# audio_V1.net
KiCad netlist of a schematic drawn in EAGLE
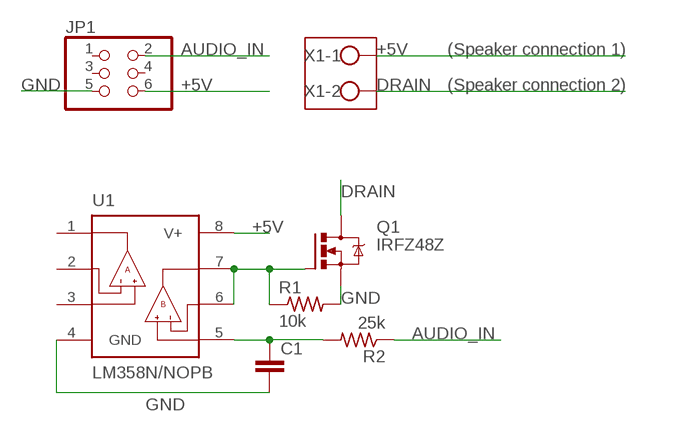
[diagram p0: schematic, sheet 1]

(export (version "E")
  (design (tool "Eeschema 10.0.6"))
  (components
    (comp (ref "C1")
      (value "C-EU025-025X050")
      (footprint "eagle-import:C025-025X050")
      (libsource (lib "eagle-import") (part "C-EU025-025X050"))
    )
    (comp (ref "JP1")
      (value "PINHD-2X3")
      (footprint "eagle-import:2X03")
      (libsource (lib "eagle-import") (part "PINHD-2X3"))
    )
    (comp (ref "Q1")
      (value "IRFZ48Z")
      (footprint "eagle-import:TO220BH")
      (libsource (lib "eagle-import") (part "IRFZ48Z"))
    )
    (comp (ref "R1")
      (value "10k")
      (footprint "eagle-import:0204_7")
      (libsource (lib "eagle-import") (part "R-US_0204/7"))
    )
    (comp (ref "R2")
      (value "25k")
      (footprint "eagle-import:0204_7")
      (libsource (lib "eagle-import") (part "R-US_0204/7"))
    )
    (comp (ref "U1")
      (value "LM358N/NOPB")
      (footprint "eagle-import:DIP794W45P254L959H508Q8")
      (fields (field (name "MF") "ON Semiconductor") (field (name "MP") "LM358N"))
      (libsource (lib "eagle-import") (part "LM358N/NOPB"))
    )
    (comp (ref "X1")
      (value "W237-102")
      (footprint "eagle-import:W237-102")
      (fields (field (name "MPN") "237-102"))
      (libsource (lib "eagle-import") (part "W237-102"))
    )
  )
  (nets
    (net (code "1") (name "/+5V") (class "Default")
      (node (ref "JP1") (pin "6") (pinfunction "6_6") (pintype "passive"))
      (node (ref "U1") (pin "8") (pinfunction "V+_8") (pintype "power_in"))
      (node (ref "X1") (pin "1") (pinfunction "KL_1") (pintype "passive"))
    )
    (net (code "2") (name "/AUDIO_IN") (class "Default")
      (node (ref "JP1") (pin "2") (pinfunction "2_2") (pintype "passive"))
      (node (ref "R2") (pin "1") (pinfunction "1_1") (pintype "passive"))
    )
    (net (code "3") (name "/DRAIN") (class "Default")
      (node (ref "Q1") (pin "D") (pinfunction "D_D") (pintype "passive"))
      (node (ref "X1") (pin "2") (pinfunction "KL_2") (pintype "passive"))
    )
    (net (code "4") (name "/GND") (class "Default")
      (node (ref "C1") (pin "2") (pinfunction "2_2") (pintype "passive"))
      (node (ref "JP1") (pin "5") (pinfunction "5_5") (pintype "passive"))
      (node (ref "Q1") (pin "S") (pinfunction "S_S") (pintype "passive"))
      (node (ref "R1") (pin "2") (pinfunction "2_2") (pintype "passive"))
      (node (ref "U1") (pin "4") (pinfunction "GND_4") (pintype "power_in"))
    )
    (net (code "5") (name "Net-(U1-+INB)") (class "Default")
      (node (ref "C1") (pin "1") (pinfunction "1_1") (pintype "passive"))
      (node (ref "R2") (pin "2") (pinfunction "2_2") (pintype "passive"))
      (node (ref "U1") (pin "5") (pinfunction "+INB_5") (pintype "input"))
    )
    (net (code "6") (name "Net-(U1--INB)") (class "Default")
      (node (ref "Q1") (pin "G") (pinfunction "G_G") (pintype "passive"))
      (node (ref "R1") (pin "1") (pinfunction "1_1") (pintype "passive"))
      (node (ref "U1") (pin "6") (pinfunction "-INB_6") (pintype "input"))
      (node (ref "U1") (pin "7") (pinfunction "OUTB_7") (pintype "output"))
    )
    (net (code "7") (name "unconnected-(JP1-Pad1)") (class "Default")
      (node (ref "JP1") (pin "1") (pinfunction "1_1") (pintype "passive"))
    )
    (net (code "8") (name "unconnected-(JP1-Pad3)") (class "Default")
      (node (ref "JP1") (pin "3") (pinfunction "3_3") (pintype "passive"))
    )
    (net (code "9") (name "unconnected-(JP1-Pad4)") (class "Default")
      (node (ref "JP1") (pin "4") (pinfunction "4_4") (pintype "passive"))
    )
    (net (code "10") (name "unconnected-(U1-+INA-Pad3)") (class "Default")
      (node (ref "U1") (pin "3") (pinfunction "+INA_3") (pintype "input"))
    )
    (net (code "11") (name "unconnected-(U1--INA-Pad2)") (class "Default")
      (node (ref "U1") (pin "2") (pinfunction "-INA_2") (pintype "input"))
    )
    (net (code "12") (name "unconnected-(U1-OUTA-Pad1)") (class "Default")
      (node (ref "U1") (pin "1") (pinfunction "OUTA_1") (pintype "output"))
    )
  )
)
